# ads1299.net
KiCad netlist of a schematic drawn in Altium Designer
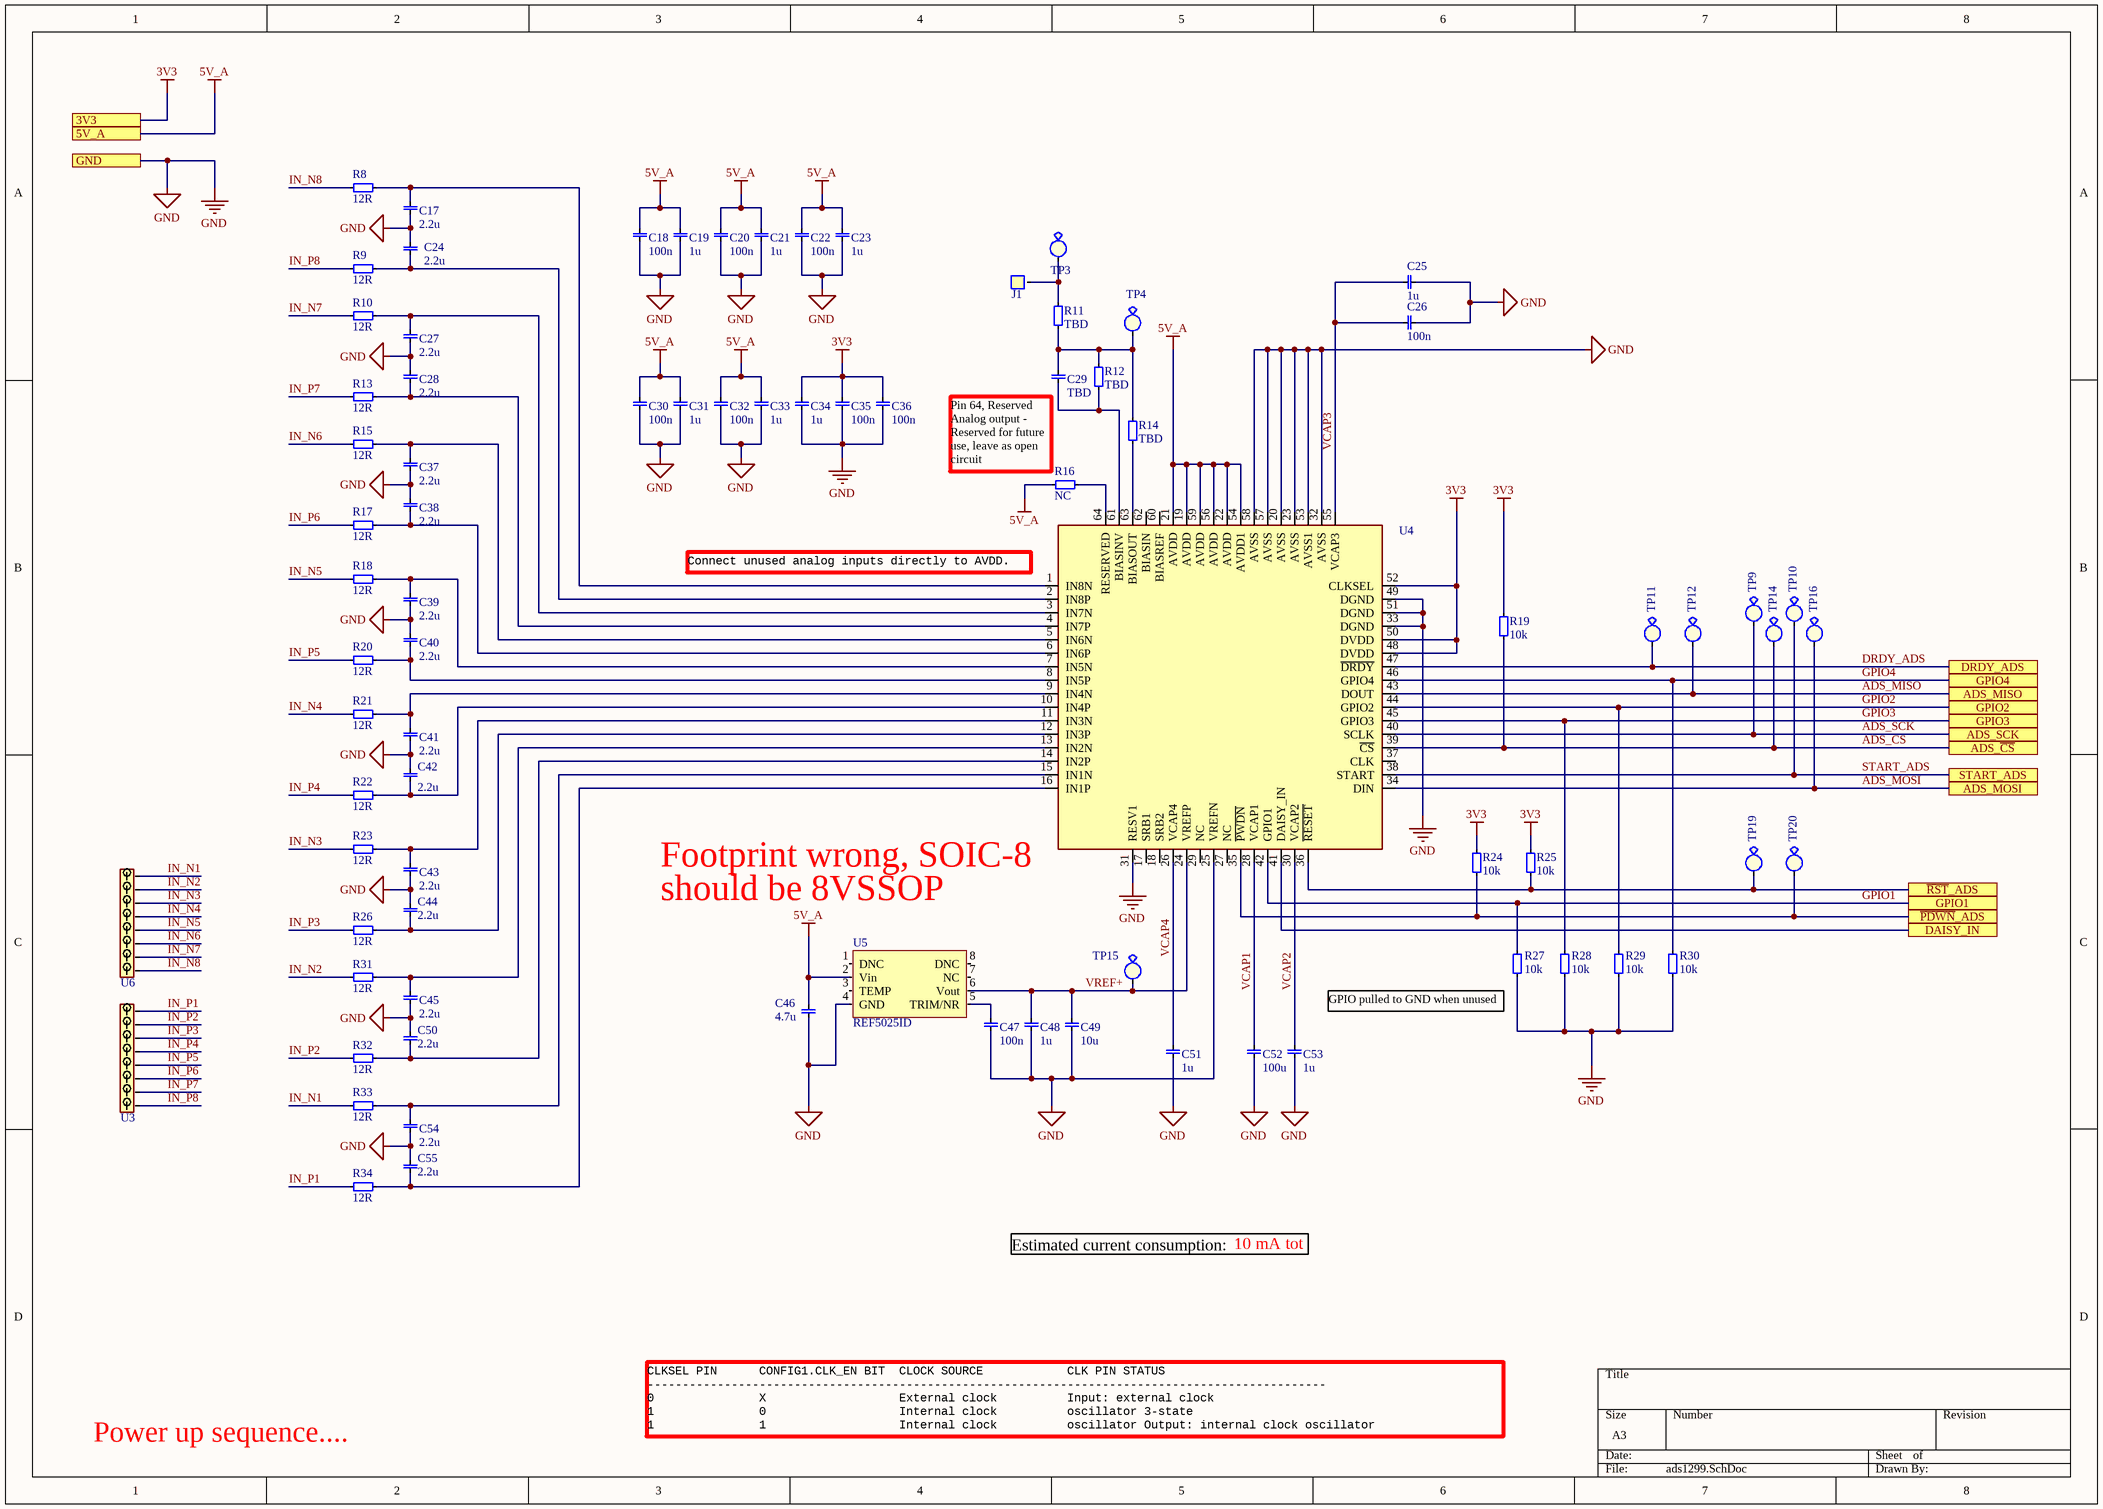
[diagram p0: ads1299.SchDoc]

(export (version "E")
  (design (tool "Eeschema 10.0.6"))
  (components
    (comp (ref "C17")
      (value "2.2u")
      (footprint "0402 CAP")
      (fields
        (field (name "MANUFACTURER PART NO") "GRM155D71A225ME15D")
        (field (name "Comment") "0603, capacitor")
      )
      (libsource (lib "jclib") (part "0603, capacitor"))
    )
    (comp (ref "C18")
      (value "100n")
      (footprint "0402 CAP")
      (fields
        (field (name "MANUFACTURER PART NO") "GRM155R62A104KE14D")
        (field (name "Comment") "0603, capacitor")
      )
      (libsource (lib "jclib") (part "0603, capacitor"))
    )
    (comp (ref "C19")
      (value "1u")
      (footprint "0402 CAP")
      (fields
        (field (name "MANUFACTURER PART NO") "CL05A105KO5NNNC")
        (field (name "Comment") "0603, capacitor")
      )
      (libsource (lib "jclib") (part "0603, capacitor"))
    )
    (comp (ref "C20")
      (value "100n")
      (footprint "0402 CAP")
      (fields
        (field (name "MANUFACTURER PART NO") "GRM155R62A104KE14D")
        (field (name "Comment") "0603, capacitor")
      )
      (libsource (lib "jclib") (part "0603, capacitor"))
    )
    (comp (ref "C21")
      (value "1u")
      (footprint "0402 CAP")
      (fields
        (field (name "MANUFACTURER PART NO") "CL05A105KO5NNNC")
        (field (name "Comment") "0603, capacitor")
      )
      (libsource (lib "jclib") (part "0603, capacitor"))
    )
    (comp (ref "C22")
      (value "100n")
      (footprint "0402 CAP")
      (fields
        (field (name "MANUFACTURER PART NO") "GRM155R62A104KE14D")
        (field (name "Comment") "0603, capacitor")
      )
      (libsource (lib "jclib") (part "0603, capacitor"))
    )
    (comp (ref "C23")
      (value "1u")
      (footprint "0402 CAP")
      (fields
        (field (name "MANUFACTURER PART NO") "CL05A105KO5NNNC")
        (field (name "Comment") "0603, capacitor")
      )
      (libsource (lib "jclib") (part "0603, capacitor"))
    )
    (comp (ref "C24")
      (value "2.2u")
      (footprint "0402 CAP")
      (fields
        (field (name "MANUFACTURER PART NO") "GRM155D71A225ME15D")
        (field (name "Comment") "0603, capacitor")
      )
      (libsource (lib "jclib") (part "0603, capacitor"))
    )
    (comp (ref "C25")
      (value "1u")
      (footprint "0402 CAP")
      (fields
        (field (name "MANUFACTURER PART NO") "CL05A105KO5NNNC")
        (field (name "Comment") "0603, capacitor")
      )
      (libsource (lib "jclib") (part "0603, capacitor"))
    )
    (comp (ref "C26")
      (value "100n")
      (footprint "0402 CAP")
      (fields
        (field (name "MANUFACTURER PART NO") "GRM155R62A104KE14D")
        (field (name "Comment") "0603, capacitor")
      )
      (libsource (lib "jclib") (part "0603, capacitor"))
    )
    (comp (ref "C27")
      (value "2.2u")
      (footprint "0402 CAP")
      (fields
        (field (name "MANUFACTURER PART NO") "GRM155D71A225ME15D")
        (field (name "Comment") "0603, capacitor")
      )
      (libsource (lib "jclib") (part "0603, capacitor"))
    )
    (comp (ref "C28")
      (value "2.2u")
      (footprint "0402 CAP")
      (fields
        (field (name "MANUFACTURER PART NO") "GRM155D71A225ME15D")
        (field (name "Comment") "0603, capacitor")
      )
      (libsource (lib "jclib") (part "0603, capacitor"))
    )
    (comp (ref "C29")
      (value "TBD")
      (footprint "0402 CAP")
      (fields (field (name "Comment") "0603, capacitor"))
      (libsource (lib "jclib") (part "0603, capacitor"))
    )
    (comp (ref "C30")
      (value "100n")
      (footprint "0402 CAP")
      (fields
        (field (name "MANUFACTURER PART NO") "GRM155R62A104KE14D")
        (field (name "Comment") "0603, capacitor")
      )
      (libsource (lib "jclib") (part "0603, capacitor"))
    )
    (comp (ref "C31")
      (value "1u")
      (footprint "0402 CAP")
      (fields
        (field (name "MANUFACTURER PART NO") "CL05A105KO5NNNC")
        (field (name "Comment") "0603, capacitor")
      )
      (libsource (lib "jclib") (part "0603, capacitor"))
    )
    (comp (ref "C32")
      (value "100n")
      (footprint "0402 CAP")
      (fields
        (field (name "MANUFACTURER PART NO") "GRM155R62A104KE14D")
        (field (name "Comment") "0603, capacitor")
      )
      (libsource (lib "jclib") (part "0603, capacitor"))
    )
    (comp (ref "C33")
      (value "1u")
      (footprint "0402 CAP")
      (fields
        (field (name "MANUFACTURER PART NO") "CL05A105KO5NNNC")
        (field (name "Comment") "0603, capacitor")
      )
      (libsource (lib "jclib") (part "0603, capacitor"))
    )
    (comp (ref "C34")
      (value "1u")
      (footprint "0402 CAP")
      (fields
        (field (name "MANUFACTURER PART NO") "CL05A105KO5NNNC")
        (field (name "Comment") "0603, capacitor")
      )
      (libsource (lib "jclib") (part "0603, capacitor"))
    )
    (comp (ref "C35")
      (value "100n")
      (footprint "0402 CAP")
      (fields
        (field (name "MANUFACTURER PART NO") "GRM155R62A104KE14D")
        (field (name "Comment") "0603, capacitor")
      )
      (libsource (lib "jclib") (part "0603, capacitor"))
    )
    (comp (ref "C36")
      (value "100n")
      (footprint "0402 CAP")
      (fields
        (field (name "MANUFACTURER PART NO") "GRM155R62A104KE14D")
        (field (name "Comment") "0603, capacitor")
      )
      (libsource (lib "jclib") (part "0603, capacitor"))
    )
    (comp (ref "C37")
      (value "2.2u")
      (footprint "0402 CAP")
      (fields
        (field (name "MANUFACTURER PART NO") "GRM155D71A225ME15D")
        (field (name "Comment") "0603, capacitor")
      )
      (libsource (lib "jclib") (part "0603, capacitor"))
    )
    (comp (ref "C38")
      (value "2.2u")
      (footprint "0402 CAP")
      (fields
        (field (name "MANUFACTURER PART NO") "GRM155D71A225ME15D")
        (field (name "Comment") "0603, capacitor")
      )
      (libsource (lib "jclib") (part "0603, capacitor"))
    )
    (comp (ref "C39")
      (value "2.2u")
      (footprint "0402 CAP")
      (fields
        (field (name "MANUFACTURER PART NO") "GRM155D71A225ME15D")
        (field (name "Comment") "0603, capacitor")
      )
      (libsource (lib "jclib") (part "0603, capacitor"))
    )
    (comp (ref "C40")
      (value "2.2u")
      (footprint "0402 CAP")
      (fields
        (field (name "MANUFACTURER PART NO") "GRM155D71A225ME15D")
        (field (name "Comment") "0603, capacitor")
      )
      (libsource (lib "jclib") (part "0603, capacitor"))
    )
    (comp (ref "C41")
      (value "2.2u")
      (footprint "0402 CAP")
      (fields
        (field (name "MANUFACTURER PART NO") "GRM155D71A225ME15D")
        (field (name "Comment") "0603, capacitor")
      )
      (libsource (lib "jclib") (part "0603, capacitor"))
    )
    (comp (ref "C42")
      (value "2.2u")
      (footprint "0402 CAP")
      (fields
        (field (name "MANUFACTURER PART NO") "GRM155D71A225ME15D")
        (field (name "Comment") "0603, capacitor")
      )
      (libsource (lib "jclib") (part "0603, capacitor"))
    )
    (comp (ref "C43")
      (value "2.2u")
      (footprint "0402 CAP")
      (fields
        (field (name "MANUFACTURER PART NO") "GRM155D71A225ME15D")
        (field (name "Comment") "0603, capacitor")
      )
      (libsource (lib "jclib") (part "0603, capacitor"))
    )
    (comp (ref "C44")
      (value "2.2u")
      (footprint "0402 CAP")
      (fields
        (field (name "MANUFACTURER PART NO") "GRM155D71A225ME15D")
        (field (name "Comment") "0603, capacitor")
      )
      (libsource (lib "jclib") (part "0603, capacitor"))
    )
    (comp (ref "C45")
      (value "2.2u")
      (footprint "0402 CAP")
      (fields
        (field (name "MANUFACTURER PART NO") "GRM155D71A225ME15D")
        (field (name "Comment") "0603, capacitor")
      )
      (libsource (lib "jclib") (part "0603, capacitor"))
    )
    (comp (ref "C46")
      (value "4.7u")
      (footprint "0402 CAP")
      (fields
        (field (name "MANUFACTURER PART NO") "04023U4R7CAT2A")
        (field (name "Comment") "0603, capacitor")
      )
      (libsource (lib "jclib") (part "0603, capacitor"))
    )
    (comp (ref "C47")
      (value "100n")
      (footprint "0402 CAP")
      (fields
        (field (name "MANUFACTURER PART NO") "GRM155R62A104KE14D")
        (field (name "Comment") "0603, capacitor")
      )
      (libsource (lib "jclib") (part "0603, capacitor"))
    )
    (comp (ref "C48")
      (value "1u")
      (footprint "0402 CAP")
      (fields
        (field (name "MANUFACTURER PART NO") "CL05A105KO5NNNC")
        (field (name "Comment") "0603, capacitor")
      )
      (libsource (lib "jclib") (part "0603, capacitor"))
    )
    (comp (ref "C49")
      (value "10u")
      (footprint "0402 CAP")
      (fields
        (field (name "MANUFACTURER PART NO") "GRM155R61A106ME11D")
        (field (name "Comment") "0603, capacitor")
      )
      (libsource (lib "jclib") (part "0603, capacitor"))
    )
    (comp (ref "C50")
      (value "2.2u")
      (footprint "0402 CAP")
      (fields
        (field (name "MANUFACTURER PART NO") "GRM155D71A225ME15D")
        (field (name "Comment") "0603, capacitor")
      )
      (libsource (lib "jclib") (part "0603, capacitor"))
    )
    (comp (ref "C51")
      (value "1u")
      (footprint "0402 CAP")
      (fields
        (field (name "MANUFACTURER PART NO") "CL05A105KO5NNNC")
        (field (name "Comment") "0603, capacitor")
      )
      (libsource (lib "jclib") (part "0603, capacitor"))
    )
    (comp (ref "C52")
      (value "100u")
      (footprint "1210, cap")
      (fields
        (field (name "MANUFACTURER PART NO") "EMK325ABJ107MM-T")
        (field (name "Comment") "1210, capacitor")
      )
      (libsource (lib "jclib") (part "1210, capacitor"))
    )
    (comp (ref "C53")
      (value "1u")
      (footprint "0402 CAP")
      (fields
        (field (name "MANUFACTURER PART NO") "CL05A105KO5NNNC")
        (field (name "Comment") "0603, capacitor")
      )
      (libsource (lib "jclib") (part "0603, capacitor"))
    )
    (comp (ref "C54")
      (value "2.2u")
      (footprint "0402 CAP")
      (fields
        (field (name "MANUFACTURER PART NO") "GRM155D71A225ME15D")
        (field (name "Comment") "0603, capacitor")
      )
      (libsource (lib "jclib") (part "0603, capacitor"))
    )
    (comp (ref "C55")
      (value "2.2u")
      (footprint "0402 CAP")
      (fields
        (field (name "MANUFACTURER PART NO") "GRM155D71A225ME15D")
        (field (name "Comment") "0603, capacitor")
      )
      (libsource (lib "jclib") (part "0603, capacitor"))
    )
    (comp (ref "J1")
      (value "1x1 Mini binding post")
      (footprint "1_pin_binding_post")
      (description "1 Pin Binding Post M2.5 Through Hole")
      (fields (field (name "MANUFACTURER PART NO") "8730"))
      (libsource (lib "jclib") (part "1x1 Mini binding post"))
    )
    (comp (ref "R8")
      (value "12R")
      (footprint "0402 res")
      (fields
        (field (name "MANUFACTURER PART NO") "RC0402FR-0712RL")
        (field (name "Comment") "0603, resistor")
      )
      (libsource (lib "jclib") (part "0603, resistor"))
    )
    (comp (ref "R9")
      (value "12R")
      (footprint "0402 res")
      (fields
        (field (name "MANUFACTURER PART NO") "RC0402FR-0712RL")
        (field (name "Comment") "0603, resistor")
      )
      (libsource (lib "jclib") (part "0603, resistor"))
    )
    (comp (ref "R10")
      (value "12R")
      (footprint "0402 res")
      (fields
        (field (name "MANUFACTURER PART NO") "RC0402FR-0712RL")
        (field (name "Comment") "0603, resistor")
      )
      (libsource (lib "jclib") (part "0603, resistor"))
    )
    (comp (ref "R11")
      (value "TBD")
      (footprint "0402 res")
      (fields (field (name "Comment") "0603, resistor"))
      (libsource (lib "jclib") (part "0603, resistor"))
    )
    (comp (ref "R12")
      (value "TBD")
      (footprint "0402 res")
      (fields (field (name "Comment") "0603, resistor"))
      (libsource (lib "jclib") (part "0603, resistor"))
    )
    (comp (ref "R13")
      (value "12R")
      (footprint "0402 res")
      (fields
        (field (name "MANUFACTURER PART NO") "RC0402FR-0712RL")
        (field (name "Comment") "0603, resistor")
      )
      (libsource (lib "jclib") (part "0603, resistor"))
    )
    (comp (ref "R14")
      (value "TBD")
      (footprint "0402 res")
      (fields (field (name "Comment") "0603, resistor"))
      (libsource (lib "jclib") (part "0603, resistor"))
    )
    (comp (ref "R15")
      (value "12R")
      (footprint "0402 res")
      (fields
        (field (name "MANUFACTURER PART NO") "RC0402FR-0712RL")
        (field (name "Comment") "0603, resistor")
      )
      (libsource (lib "jclib") (part "0603, resistor"))
    )
    (comp (ref "R16")
      (value "NC")
      (footprint "0402 res")
      (fields (field (name "Comment") "0603, resistor"))
      (libsource (lib "jclib") (part "0603, resistor"))
    )
    (comp (ref "R17")
      (value "12R")
      (footprint "0402 res")
      (fields
        (field (name "MANUFACTURER PART NO") "RC0402FR-0712RL")
        (field (name "Comment") "0603, resistor")
      )
      (libsource (lib "jclib") (part "0603, resistor"))
    )
    (comp (ref "R18")
      (value "12R")
      (footprint "0402 res")
      (fields
        (field (name "MANUFACTURER PART NO") "RC0402FR-0712RL")
        (field (name "Comment") "0603, resistor")
      )
      (libsource (lib "jclib") (part "0603, resistor"))
    )
    (comp (ref "R19")
      (value "10k")
      (footprint "0402 res")
      (fields
        (field (name "MANUFACTURER PART NO") "311-10.0KLRCT-ND")
        (field (name "Comment") "0603, resistor")
      )
      (libsource (lib "jclib") (part "0603, resistor"))
    )
    (comp (ref "R20")
      (value "12R")
      (footprint "0402 res")
      (fields
        (field (name "MANUFACTURER PART NO") "RC0402FR-0712RL")
        (field (name "Comment") "0603, resistor")
      )
      (libsource (lib "jclib") (part "0603, resistor"))
    )
    (comp (ref "R21")
      (value "12R")
      (footprint "0402 res")
      (fields
        (field (name "MANUFACTURER PART NO") "RC0402FR-0712RL")
        (field (name "Comment") "0603, resistor")
      )
      (libsource (lib "jclib") (part "0603, resistor"))
    )
    (comp (ref "R22")
      (value "12R")
      (footprint "0402 res")
      (fields
        (field (name "MANUFACTURER PART NO") "RC0402FR-0712RL")
        (field (name "Comment") "0603, resistor")
      )
      (libsource (lib "jclib") (part "0603, resistor"))
    )
    (comp (ref "R23")
      (value "12R")
      (footprint "0402 res")
      (fields
        (field (name "MANUFACTURER PART NO") "RC0402FR-0712RL")
        (field (name "Comment") "0603, resistor")
      )
      (libsource (lib "jclib") (part "0603, resistor"))
    )
    (comp (ref "R24")
      (value "10k")
      (footprint "0402 res")
      (fields
        (field (name "MANUFACTURER PART NO") "311-10.0KLRCT-ND")
        (field (name "Comment") "0603, resistor")
      )
      (libsource (lib "jclib") (part "0603, resistor"))
    )
    (comp (ref "R25")
      (value "10k")
      (footprint "0402 res")
      (fields
        (field (name "MANUFACTURER PART NO") "311-10.0KLRCT-ND")
        (field (name "Comment") "0603, resistor")
      )
      (libsource (lib "jclib") (part "0603, resistor"))
    )
    (comp (ref "R26")
      (value "12R")
      (footprint "0402 res")
      (fields
        (field (name "MANUFACTURER PART NO") "RC0402FR-0712RL")
        (field (name "Comment") "0603, resistor")
      )
      (libsource (lib "jclib") (part "0603, resistor"))
    )
    (comp (ref "R27")
      (value "10k")
      (footprint "0402 res")
      (fields
        (field (name "MANUFACTURER PART NO") "311-10.0KLRCT-ND")
        (field (name "Comment") "0603, resistor")
      )
      (libsource (lib "jclib") (part "0603, resistor"))
    )
    (comp (ref "R28")
      (value "10k")
      (footprint "0402 res")
      (fields
        (field (name "MANUFACTURER PART NO") "311-10.0KLRCT-ND")
        (field (name "Comment") "0603, resistor")
      )
      (libsource (lib "jclib") (part "0603, resistor"))
    )
    (comp (ref "R29")
      (value "10k")
      (footprint "0402 res")
      (fields
        (field (name "MANUFACTURER PART NO") "311-10.0KLRCT-ND")
        (field (name "Comment") "0603, resistor")
      )
      (libsource (lib "jclib") (part "0603, resistor"))
    )
    (comp (ref "R30")
      (value "10k")
      (footprint "0402 res")
      (fields
        (field (name "MANUFACTURER PART NO") "311-10.0KLRCT-ND")
        (field (name "Comment") "0603, resistor")
      )
      (libsource (lib "jclib") (part "0603, resistor"))
    )
    (comp (ref "R31")
      (value "12R")
      (footprint "0402 res")
      (fields
        (field (name "MANUFACTURER PART NO") "RC0402FR-0712RL")
        (field (name "Comment") "0603, resistor")
      )
      (libsource (lib "jclib") (part "0603, resistor"))
    )
    (comp (ref "R32")
      (value "12R")
      (footprint "0402 res")
      (fields
        (field (name "MANUFACTURER PART NO") "RC0402FR-0712RL")
        (field (name "Comment") "0603, resistor")
      )
      (libsource (lib "jclib") (part "0603, resistor"))
    )
    (comp (ref "R33")
      (value "12R")
      (footprint "0402 res")
      (fields
        (field (name "MANUFACTURER PART NO") "RC0402FR-0712RL")
        (field (name "Comment") "0603, resistor")
      )
      (libsource (lib "jclib") (part "0603, resistor"))
    )
    (comp (ref "R34")
      (value "12R")
      (footprint "0402 res")
      (fields
        (field (name "MANUFACTURER PART NO") "RC0402FR-0712RL")
        (field (name "Comment") "0603, resistor")
      )
      (libsource (lib "jclib") (part "0603, resistor"))
    )
    (comp (ref "TP3")
      (value "Test Point")
      (footprint "TESTPOINT_SMD")
      (libsource (lib "jclib") (part "Test Point"))
    )
    (comp (ref "TP4")
      (value "Test Point")
      (footprint "TESTPOINT_SMD")
      (libsource (lib "jclib") (part "Test Point"))
    )
    (comp (ref "TP9")
      (value "Test Point")
      (footprint "TESTPOINT_SMD")
      (libsource (lib "jclib") (part "Test Point"))
    )
    (comp (ref "TP10")
      (value "Test Point")
      (footprint "TESTPOINT_SMD")
      (libsource (lib "jclib") (part "Test Point"))
    )
    (comp (ref "TP11")
      (value "Test Point")
      (footprint "TESTPOINT_SMD")
      (libsource (lib "jclib") (part "Test Point"))
    )
    (comp (ref "TP12")
      (value "Test Point")
      (footprint "TESTPOINT_SMD")
      (libsource (lib "jclib") (part "Test Point"))
    )
    (comp (ref "TP14")
      (value "Test Point")
      (footprint "TESTPOINT_SMD")
      (libsource (lib "jclib") (part "Test Point"))
    )
    (comp (ref "TP15")
      (value "Test Point")
      (footprint "TESTPOINT_SMD")
      (libsource (lib "jclib") (part "Test Point"))
    )
    (comp (ref "TP16")
      (value "Test Point")
      (footprint "TESTPOINT_SMD")
      (libsource (lib "jclib") (part "Test Point"))
    )
    (comp (ref "TP19")
      (value "Test Point")
      (footprint "TESTPOINT_SMD")
      (libsource (lib "jclib") (part "Test Point"))
    )
    (comp (ref "TP20")
      (value "Test Point")
      (footprint "TESTPOINT_SMD")
      (libsource (lib "jclib") (part "Test Point"))
    )
    (comp (ref "U3")
      (value "1x8 Screw terminal")
      (footprint "screw_term_8_pos")
      (fields (field (name "MANUFACTURER PART NO") "OSTVN08A150"))
      (libsource (lib "") (part "1x8 Screw terminal_1"))
    )
    (comp (ref "U4")
      (value "ADS1299")
      (footprint "TQFP64_05MM_P")
      (description "24-Bit, Analog-to-Digital Converter for EEG and\r\nBiopotential Measurements")
      (fields (field (name "MANUFACTURER PART NO") "ADS1299IPAG"))
      (libsource (lib "jclib") (part "ADS1299"))
    )
    (comp (ref "U5")
      (value "REF5025ID")
      (footprint "SOP65P490X110-8N")
      (libsource (lib "jclib") (part "REF5025ID"))
    )
    (comp (ref "U6")
      (value "1x8 Screw terminal")
      (footprint "screw_term_8_pos")
      (fields (field (name "MANUFACTURER PART NO") "OSTVN08A150"))
      (libsource (lib "jclib") (part "1x8 Screw terminal"))
    )
  )
  (nets
    (net (code "1") (name "/ADS_MISO") (class "Default")
      (node (ref "TP12") (pin "0") (pinfunction "0_0") (pintype "passive"))
      (node (ref "U4") (pin "43") (pinfunction "DOUT_43") (pintype "passive"))
    )
    (net (code "2") (name "/ADS_MOSI") (class "Default")
      (node (ref "TP16") (pin "0") (pinfunction "0_0") (pintype "passive"))
      (node (ref "U4") (pin "34") (pinfunction "DIN_34") (pintype "passive"))
    )
    (net (code "3") (name "/ADS_SCK") (class "Default")
      (node (ref "TP9") (pin "0") (pinfunction "0_0") (pintype "passive"))
      (node (ref "U4") (pin "40") (pinfunction "SCLK_40") (pintype "passive"))
    )
    (net (code "4") (name "/ADS_~{CS}") (class "Default")
      (node (ref "R19") (pin "1") (pinfunction "1_1") (pintype "passive"))
      (node (ref "TP14") (pin "0") (pinfunction "0_0") (pintype "passive"))
      (node (ref "U4") (pin "39") (pinfunction "~{CS}_39") (pintype "passive"))
    )
    (net (code "5") (name "/DAISY_IN") (class "Default")
      (node (ref "U4") (pin "41") (pinfunction "DAISY_IN_41") (pintype "passive"))
    )
    (net (code "6") (name "/DRDY_ADS") (class "Default")
      (node (ref "TP11") (pin "0") (pinfunction "0_0") (pintype "passive"))
      (node (ref "U4") (pin "47") (pinfunction "~{DRDY}_47") (pintype "passive"))
    )
    (net (code "7") (name "/GPIO1") (class "Default")
      (node (ref "R27") (pin "0") (pinfunction "0_0") (pintype "passive"))
      (node (ref "U4") (pin "42") (pinfunction "GPIO1_42") (pintype "passive"))
    )
    (net (code "8") (name "/GPIO2") (class "Default")
      (node (ref "R29") (pin "0") (pinfunction "0_0") (pintype "passive"))
      (node (ref "U4") (pin "44") (pinfunction "GPIO2_44") (pintype "passive"))
    )
    (net (code "9") (name "/GPIO3") (class "Default")
      (node (ref "R28") (pin "0") (pinfunction "0_0") (pintype "passive"))
      (node (ref "U4") (pin "45") (pinfunction "GPIO3_45") (pintype "passive"))
    )
    (net (code "10") (name "/GPIO4") (class "Default")
      (node (ref "R30") (pin "0") (pinfunction "0_0") (pintype "passive"))
      (node (ref "U4") (pin "46") (pinfunction "GPIO4_46") (pintype "passive"))
    )
    (net (code "11") (name "/IN_N1") (class "Default")
      (node (ref "R33") (pin "1") (pinfunction "1_1") (pintype "passive"))
      (node (ref "U6") (pin "1") (pinfunction "1_1") (pintype "passive"))
    )
    (net (code "12") (name "/IN_N2") (class "Default")
      (node (ref "R31") (pin "1") (pinfunction "1_1") (pintype "passive"))
      (node (ref "U6") (pin "2") (pinfunction "2_2") (pintype "passive"))
    )
    (net (code "13") (name "/IN_N3") (class "Default")
      (node (ref "R23") (pin "1") (pinfunction "1_1") (pintype "passive"))
      (node (ref "U6") (pin "3") (pinfunction "3_3") (pintype "passive"))
    )
    (net (code "14") (name "/IN_N4") (class "Default")
      (node (ref "R21") (pin "1") (pinfunction "1_1") (pintype "passive"))
      (node (ref "U6") (pin "4") (pinfunction "4_4") (pintype "passive"))
    )
    (net (code "15") (name "/IN_N5") (class "Default")
      (node (ref "R18") (pin "1") (pinfunction "1_1") (pintype "passive"))
      (node (ref "U6") (pin "5") (pinfunction "5_5") (pintype "passive"))
    )
    (net (code "16") (name "/IN_N6") (class "Default")
      (node (ref "R15") (pin "1") (pinfunction "1_1") (pintype "passive"))
      (node (ref "U6") (pin "6") (pinfunction "6_6") (pintype "passive"))
    )
    (net (code "17") (name "/IN_N7") (class "Default")
      (node (ref "R10") (pin "1") (pinfunction "1_1") (pintype "passive"))
      (node (ref "U6") (pin "7") (pinfunction "7_7") (pintype "passive"))
    )
    (net (code "18") (name "/IN_N8") (class "Default")
      (node (ref "R8") (pin "1") (pinfunction "1_1") (pintype "passive"))
      (node (ref "U6") (pin "8") (pinfunction "8_8") (pintype "passive"))
    )
    (net (code "19") (name "/IN_P1") (class "Default")
      (node (ref "R34") (pin "1") (pinfunction "1_1") (pintype "passive"))
      (node (ref "U3") (pin "8") (pinfunction "8_8") (pintype "passive"))
    )
    (net (code "20") (name "/IN_P2") (class "Default")
      (node (ref "R32") (pin "1") (pinfunction "1_1") (pintype "passive"))
      (node (ref "U3") (pin "7") (pinfunction "7_7") (pintype "passive"))
    )
    (net (code "21") (name "/IN_P3") (class "Default")
      (node (ref "R26") (pin "1") (pinfunction "1_1") (pintype "passive"))
      (node (ref "U3") (pin "6") (pinfunction "6_6") (pintype "passive"))
    )
    (net (code "22") (name "/IN_P4") (class "Default")
      (node (ref "R22") (pin "1") (pinfunction "1_1") (pintype "passive"))
      (node (ref "U3") (pin "5") (pinfunction "5_5") (pintype "passive"))
    )
    (net (code "23") (name "/IN_P5") (class "Default")
      (node (ref "R20") (pin "1") (pinfunction "1_1") (pintype "passive"))
      (node (ref "U3") (pin "4") (pinfunction "4_4") (pintype "passive"))
    )
    (net (code "24") (name "/IN_P6") (class "Default")
      (node (ref "R17") (pin "1") (pinfunction "1_1") (pintype "passive"))
      (node (ref "U3") (pin "3") (pinfunction "3_3") (pintype "passive"))
    )
    (net (code "25") (name "/IN_P7") (class "Default")
      (node (ref "R13") (pin "1") (pinfunction "1_1") (pintype "passive"))
      (node (ref "U3") (pin "2") (pinfunction "2_2") (pintype "passive"))
    )
    (net (code "26") (name "/IN_P8") (class "Default")
      (node (ref "R9") (pin "1") (pinfunction "1_1") (pintype "passive"))
      (node (ref "U3") (pin "1") (pinfunction "1_1") (pintype "passive"))
    )
    (net (code "27") (name "/START_ADS") (class "Default")
      (node (ref "TP10") (pin "0") (pinfunction "0_0") (pintype "passive"))
      (node (ref "U4") (pin "38") (pinfunction "START_38") (pintype "passive"))
    )
    (net (code "28") (name "/VCAP1") (class "Default")
      (node (ref "C52") (pin "1") (pinfunction "1_1") (pintype "passive"))
      (node (ref "U4") (pin "28") (pinfunction "VCAP1_28") (pintype "passive"))
    )
    (net (code "29") (name "/VCAP2") (class "Default")
      (node (ref "C53") (pin "1") (pinfunction "1_1") (pintype "passive"))
      (node (ref "U4") (pin "30") (pinfunction "VCAP2_30") (pintype "passive"))
    )
    (net (code "30") (name "/VCAP3") (class "Default")
      (node (ref "C25") (pin "1") (pinfunction "1_1") (pintype "passive"))
      (node (ref "C26") (pin "1") (pinfunction "1_1") (pintype "passive"))
      (node (ref "U4") (pin "55") (pinfunction "VCAP3_55") (pintype "passive"))
    )
    (net (code "31") (name "/VCAP4") (class "Default")
      (node (ref "C51") (pin "1") (pinfunction "1_1") (pintype "passive"))
      (node (ref "U4") (pin "26") (pinfunction "VCAP4_26") (pintype "passive"))
    )
    (net (code "32") (name "/VREF+") (class "Default")
      (node (ref "C48") (pin "1") (pinfunction "1_1") (pintype "passive"))
      (node (ref "C49") (pin "1") (pinfunction "1_1") (pintype "passive"))
      (node (ref "TP15") (pin "0") (pinfunction "0_0") (pintype "passive"))
      (node (ref "U4") (pin "24") (pinfunction "VREFP_24") (pintype "passive"))
      (node (ref "U5") (pin "6") (pinfunction "Vout_6") (pintype "passive"))
    )
    (net (code "33") (name "/~{PDWN}_ADS") (class "Default")
      (node (ref "R24") (pin "1") (pinfunction "1_1") (pintype "passive"))
      (node (ref "TP20") (pin "0") (pinfunction "0_0") (pintype "passive"))
      (node (ref "U4") (pin "35") (pinfunction "~{PWDN}_35") (pintype "passive"))
    )
    (net (code "34") (name "/~{RST}_ADS") (class "Default")
      (node (ref "R25") (pin "1") (pinfunction "1_1") (pintype "passive"))
      (node (ref "TP19") (pin "0") (pinfunction "0_0") (pintype "passive"))
      (node (ref "U4") (pin "36") (pinfunction "~{RESET}_36") (pintype "passive"))
    )
    (net (code "35") (name "3V3") (class "Default")
      (node (ref "C34") (pin "1") (pinfunction "1_1") (pintype "passive"))
      (node (ref "C35") (pin "1") (pinfunction "1_1") (pintype "passive"))
      (node (ref "C36") (pin "1") (pinfunction "1_1") (pintype "passive"))
      (node (ref "R19") (pin "0") (pinfunction "0_0") (pintype "passive"))
      (node (ref "R24") (pin "0") (pinfunction "0_0") (pintype "passive"))
      (node (ref "R25") (pin "0") (pinfunction "0_0") (pintype "passive"))
      (node (ref "U4") (pin "48") (pinfunction "DVDD_48") (pintype "passive"))
      (node (ref "U4") (pin "50") (pinfunction "DVDD_50") (pintype "passive"))
      (node (ref "U4") (pin "52") (pinfunction "CLKSEL_52") (pintype "passive"))
    )
    (net (code "36") (name "5V_A") (class "Default")
      (node (ref "C18") (pin "1") (pinfunction "1_1") (pintype "passive"))
      (node (ref "C19") (pin "1") (pinfunction "1_1") (pintype "passive"))
      (node (ref "C20") (pin "1") (pinfunction "1_1") (pintype "passive"))
      (node (ref "C21") (pin "1") (pinfunction "1_1") (pintype "passive"))
      (node (ref "C22") (pin "1") (pinfunction "1_1") (pintype "passive"))
      (node (ref "C23") (pin "1") (pinfunction "1_1") (pintype "passive"))
      (node (ref "C30") (pin "1") (pinfunction "1_1") (pintype "passive"))
      (node (ref "C31") (pin "1") (pinfunction "1_1") (pintype "passive"))
      (node (ref "C32") (pin "1") (pinfunction "1_1") (pintype "passive"))
      (node (ref "C33") (pin "1") (pinfunction "1_1") (pintype "passive"))
      (node (ref "C46") (pin "1") (pinfunction "1_1") (pintype "passive"))
      (node (ref "R16") (pin "0") (pinfunction "0_0") (pintype "passive"))
      (node (ref "U4") (pin "19") (pinfunction "AVDD_19") (pintype "passive"))
      (node (ref "U4") (pin "21") (pinfunction "AVDD_21") (pintype "passive"))
      (node (ref "U4") (pin "22") (pinfunction "AVDD_22") (pintype "passive"))
      (node (ref "U4") (pin "54") (pinfunction "AVDD1_54") (pintype "passive"))
      (node (ref "U4") (pin "56") (pinfunction "AVDD_56") (pintype "passive"))
      (node (ref "U4") (pin "59") (pinfunction "AVDD_59") (pintype "passive"))
      (node (ref "U5") (pin "2") (pinfunction "Vin_2") (pintype "passive"))
    )
    (net (code "37") (name "GND") (class "Default")
      (node (ref "C17") (pin "0") (pinfunction "0_0") (pintype "passive"))
      (node (ref "C18") (pin "0") (pinfunction "0_0") (pintype "passive"))
      (node (ref "C19") (pin "0") (pinfunction "0_0") (pintype "passive"))
      (node (ref "C20") (pin "0") (pinfunction "0_0") (pintype "passive"))
      (node (ref "C21") (pin "0") (pinfunction "0_0") (pintype "passive"))
      (node (ref "C22") (pin "0") (pinfunction "0_0") (pintype "passive"))
      (node (ref "C23") (pin "0") (pinfunction "0_0") (pintype "passive"))
      (node (ref "C24") (pin "0") (pinfunction "0_0") (pintype "passive"))
      (node (ref "C25") (pin "0") (pinfunction "0_0") (pintype "passive"))
      (node (ref "C26") (pin "0") (pinfunction "0_0") (pintype "passive"))
      (node (ref "C27") (pin "0") (pinfunction "0_0") (pintype "passive"))
      (node (ref "C28") (pin "0") (pinfunction "0_0") (pintype "passive"))
      (node (ref "C30") (pin "0") (pinfunction "0_0") (pintype "passive"))
      (node (ref "C31") (pin "0") (pinfunction "0_0") (pintype "passive"))
      (node (ref "C32") (pin "0") (pinfunction "0_0") (pintype "passive"))
      (node (ref "C33") (pin "0") (pinfunction "0_0") (pintype "passive"))
      (node (ref "C34") (pin "0") (pinfunction "0_0") (pintype "passive"))
      (node (ref "C35") (pin "0") (pinfunction "0_0") (pintype "passive"))
      (node (ref "C36") (pin "0") (pinfunction "0_0") (pintype "passive"))
      (node (ref "C37") (pin "0") (pinfunction "0_0") (pintype "passive"))
      (node (ref "C38") (pin "0") (pinfunction "0_0") (pintype "passive"))
      (node (ref "C39") (pin "0") (pinfunction "0_0") (pintype "passive"))
      (node (ref "C40") (pin "0") (pinfunction "0_0") (pintype "passive"))
      (node (ref "C41") (pin "0") (pinfunction "0_0") (pintype "passive"))
      (node (ref "C42") (pin "0") (pinfunction "0_0") (pintype "passive"))
      (node (ref "C43") (pin "0") (pinfunction "0_0") (pintype "passive"))
      (node (ref "C44") (pin "0") (pinfunction "0_0") (pintype "passive"))
      (node (ref "C45") (pin "0") (pinfunction "0_0") (pintype "passive"))
      (node (ref "C46") (pin "0") (pinfunction "0_0") (pintype "passive"))
      (node (ref "C47") (pin "0") (pinfunction "0_0") (pintype "passive"))
      (node (ref "C48") (pin "0") (pinfunction "0_0") (pintype "passive"))
      (node (ref "C49") (pin "0") (pinfunction "0_0") (pintype "passive"))
      (node (ref "C50") (pin "0") (pinfunction "0_0") (pintype "passive"))
      (node (ref "C51") (pin "0") (pinfunction "0_0") (pintype "passive"))
      (node (ref "C52") (pin "0") (pinfunction "0_0") (pintype "passive"))
      (node (ref "C53") (pin "0") (pinfunction "0_0") (pintype "passive"))
      (node (ref "C54") (pin "0") (pinfunction "0_0") (pintype "passive"))
      (node (ref "C55") (pin "0") (pinfunction "0_0") (pintype "passive"))
      (node (ref "R27") (pin "1") (pinfunction "1_1") (pintype "passive"))
      (node (ref "R28") (pin "1") (pinfunction "1_1") (pintype "passive"))
      (node (ref "R29") (pin "1") (pinfunction "1_1") (pintype "passive"))
      (node (ref "R30") (pin "1") (pinfunction "1_1") (pintype "passive"))
      (node (ref "U4") (pin "20") (pinfunction "AVSS_20") (pintype "passive"))
      (node (ref "U4") (pin "23") (pinfunction "AVSS_23") (pintype "passive"))
      (node (ref "U4") (pin "25") (pinfunction "VREFN_25") (pintype "passive"))
      (node (ref "U4") (pin "31") (pinfunction "RESV1_31") (pintype "passive"))
      (node (ref "U4") (pin "32") (pinfunction "AVSS_32") (pintype "passive"))
      (node (ref "U4") (pin "33") (pinfunction "DGND_33") (pintype "passive"))
      (node (ref "U4") (pin "49") (pinfunction "DGND_49") (pintype "passive"))
      (node (ref "U4") (pin "51") (pinfunction "DGND_51") (pintype "passive"))
      (node (ref "U4") (pin "53") (pinfunction "AVSS1_53") (pintype "passive"))
      (node (ref "U4") (pin "57") (pinfunction "AVSS_57") (pintype "passive"))
      (node (ref "U4") (pin "58") (pinfunction "AVSS_58") (pintype "passive"))
      (node (ref "U5") (pin "4") (pinfunction "GND_4") (pintype "passive"))
    )
    (net (code "38") (name "Net-(C29-Pad1)") (class "Default")
      (node (ref "C29") (pin "1") (pinfunction "1_1") (pintype "passive"))
      (node (ref "R11") (pin "1") (pinfunction "1_1") (pintype "passive"))
      (node (ref "R12") (pin "0") (pinfunction "0_0") (pintype "passive"))
      (node (ref "R14") (pin "0") (pinfunction "0_0") (pintype "passive"))
      (node (ref "TP4") (pin "0") (pinfunction "0_0") (pintype "passive"))
    )
    (net (code "39") (name "Net-(J1-Pad1)") (class "Default")
      (node (ref "J1") (pin "1") (pinfunction "1_1") (pintype "passive"))
      (node (ref "R11") (pin "0") (pinfunction "0_0") (pintype "passive"))
      (node (ref "TP3") (pin "0") (pinfunction "0_0") (pintype "passive"))
    )
    (net (code "40") (name "Net-(U4-BIASINV)") (class "Default")
      (node (ref "C29") (pin "0") (pinfunction "0_0") (pintype "passive"))
      (node (ref "R12") (pin "1") (pinfunction "1_1") (pintype "passive"))
      (node (ref "U4") (pin "61") (pinfunction "BIASINV_61") (pintype "passive"))
    )
    (net (code "41") (name "Net-(U4-BIASOUT)") (class "Default")
      (node (ref "R14") (pin "1") (pinfunction "1_1") (pintype "passive"))
      (node (ref "U4") (pin "63") (pinfunction "BIASOUT_63") (pintype "passive"))
    )
    (net (code "42") (name "Net-(U4-IN1N)") (class "Default")
      (node (ref "C54") (pin "1") (pinfunction "1_1") (pintype "passive"))
      (node (ref "R33") (pin "0") (pinfunction "0_0") (pintype "passive"))
      (node (ref "U4") (pin "15") (pinfunction "IN1N_15") (pintype "passive"))
    )
    (net (code "43") (name "Net-(U4-IN1P)") (class "Default")
      (node (ref "C55") (pin "1") (pinfunction "1_1") (pintype "passive"))
      (node (ref "R34") (pin "0") (pinfunction "0_0") (pintype "passive"))
      (node (ref "U4") (pin "16") (pinfunction "IN1P_16") (pintype "passive"))
    )
    (net (code "44") (name "Net-(U4-IN2N)") (class "Default")
      (node (ref "C45") (pin "1") (pinfunction "1_1") (pintype "passive"))
      (node (ref "R31") (pin "0") (pinfunction "0_0") (pintype "passive"))
      (node (ref "U4") (pin "13") (pinfunction "IN2N_13") (pintype "passive"))
    )
    (net (code "45") (name "Net-(U4-IN2P)") (class "Default")
      (node (ref "C50") (pin "1") (pinfunction "1_1") (pintype "passive"))
      (node (ref "R32") (pin "0") (pinfunction "0_0") (pintype "passive"))
      (node (ref "U4") (pin "14") (pinfunction "IN2P_14") (pintype "passive"))
    )
    (net (code "46") (name "Net-(U4-IN3N)") (class "Default")
      (node (ref "C43") (pin "1") (pinfunction "1_1") (pintype "passive"))
      (node (ref "R23") (pin "0") (pinfunction "0_0") (pintype "passive"))
      (node (ref "U4") (pin "11") (pinfunction "IN3N_11") (pintype "passive"))
    )
    (net (code "47") (name "Net-(U4-IN3P)") (class "Default")
      (node (ref "C44") (pin "1") (pinfunction "1_1") (pintype "passive"))
      (node (ref "R26") (pin "0") (pinfunction "0_0") (pintype "passive"))
      (node (ref "U4") (pin "12") (pinfunction "IN3P_12") (pintype "passive"))
    )
    (net (code "48") (name "Net-(U4-IN4N)") (class "Default")
      (node (ref "C41") (pin "1") (pinfunction "1_1") (pintype "passive"))
      (node (ref "R21") (pin "0") (pinfunction "0_0") (pintype "passive"))
      (node (ref "U4") (pin "9") (pinfunction "IN4N_9") (pintype "passive"))
    )
    (net (code "49") (name "Net-(U4-IN4P)") (class "Default")
      (node (ref "C42") (pin "1") (pinfunction "1_1") (pintype "passive"))
      (node (ref "R22") (pin "0") (pinfunction "0_0") (pintype "passive"))
      (node (ref "U4") (pin "10") (pinfunction "IN4P_10") (pintype "passive"))
    )
    (net (code "50") (name "Net-(U4-IN5N)") (class "Default")
      (node (ref "C39") (pin "1") (pinfunction "1_1") (pintype "passive"))
      (node (ref "R18") (pin "0") (pinfunction "0_0") (pintype "passive"))
      (node (ref "U4") (pin "7") (pinfunction "IN5N_7") (pintype "passive"))
    )
    (net (code "51") (name "Net-(U4-IN5P)") (class "Default")
      (node (ref "C40") (pin "1") (pinfunction "1_1") (pintype "passive"))
      (node (ref "R20") (pin "0") (pinfunction "0_0") (pintype "passive"))
      (node (ref "U4") (pin "8") (pinfunction "IN5P_8") (pintype "passive"))
    )
    (net (code "52") (name "Net-(U4-IN6N)") (class "Default")
      (node (ref "C37") (pin "1") (pinfunction "1_1") (pintype "passive"))
      (node (ref "R15") (pin "0") (pinfunction "0_0") (pintype "passive"))
      (node (ref "U4") (pin "5") (pinfunction "IN6N_5") (pintype "passive"))
    )
    (net (code "53") (name "Net-(U4-IN6P)") (class "Default")
      (node (ref "C38") (pin "1") (pinfunction "1_1") (pintype "passive"))
      (node (ref "R17") (pin "0") (pinfunction "0_0") (pintype "passive"))
      (node (ref "U4") (pin "6") (pinfunction "IN6P_6") (pintype "passive"))
    )
    (net (code "54") (name "Net-(U4-IN7N)") (class "Default")
      (node (ref "C27") (pin "1") (pinfunction "1_1") (pintype "passive"))
      (node (ref "R10") (pin "0") (pinfunction "0_0") (pintype "passive"))
      (node (ref "U4") (pin "3") (pinfunction "IN7N_3") (pintype "passive"))
    )
    (net (code "55") (name "Net-(U4-IN7P)") (class "Default")
      (node (ref "C28") (pin "1") (pinfunction "1_1") (pintype "passive"))
      (node (ref "R13") (pin "0") (pinfunction "0_0") (pintype "passive"))
      (node (ref "U4") (pin "4") (pinfunction "IN7P_4") (pintype "passive"))
    )
    (net (code "56") (name "Net-(U4-IN8N)") (class "Default")
      (node (ref "C17") (pin "1") (pinfunction "1_1") (pintype "passive"))
      (node (ref "R8") (pin "0") (pinfunction "0_0") (pintype "passive"))
      (node (ref "U4") (pin "1") (pinfunction "IN8N_1") (pintype "passive"))
    )
    (net (code "57") (name "Net-(U4-IN8P)") (class "Default")
      (node (ref "C24") (pin "1") (pinfunction "1_1") (pintype "passive"))
      (node (ref "R9") (pin "0") (pinfunction "0_0") (pintype "passive"))
      (node (ref "U4") (pin "2") (pinfunction "IN8P_2") (pintype "passive"))
    )
    (net (code "58") (name "Net-(U4-RESERVED)") (class "Default")
      (node (ref "R16") (pin "1") (pinfunction "1_1") (pintype "passive"))
      (node (ref "U4") (pin "64") (pinfunction "RESERVED_64") (pintype "passive"))
    )
    (net (code "59") (name "Net-(U5-TRIM{slash}NR)") (class "Default")
      (node (ref "C47") (pin "1") (pinfunction "1_1") (pintype "passive"))
      (node (ref "U5") (pin "5") (pinfunction "TRIM/NR_5") (pintype "passive"))
    )
    (net (code "60") (name "unconnected-(U4-BIASIN-Pad62)") (class "Default")
      (node (ref "U4") (pin "62") (pinfunction "BIASIN_62") (pintype "passive"))
    )
    (net (code "61") (name "unconnected-(U4-BIASREF-Pad60)") (class "Default")
      (node (ref "U4") (pin "60") (pinfunction "BIASREF_60") (pintype "passive"))
    )
    (net (code "62") (name "unconnected-(U4-CLK-Pad37)") (class "Default")
      (node (ref "U4") (pin "37") (pinfunction "CLK_37") (pintype "passive"))
    )
    (net (code "63") (name "unconnected-(U4-NC-Pad27)") (class "Default")
      (node (ref "U4") (pin "27") (pinfunction "NC_27") (pintype "passive"))
    )
    (net (code "64") (name "unconnected-(U4-NC-Pad29)") (class "Default")
      (node (ref "U4") (pin "29") (pinfunction "NC_29") (pintype "passive"))
    )
    (net (code "65") (name "unconnected-(U4-SRB1-Pad17)") (class "Default")
      (node (ref "U4") (pin "17") (pinfunction "SRB1_17") (pintype "passive"))
    )
    (net (code "66") (name "unconnected-(U4-SRB2-Pad18)") (class "Default")
      (node (ref "U4") (pin "18") (pinfunction "SRB2_18") (pintype "passive"))
    )
    (net (code "67") (name "unconnected-(U5-DNC-Pad1)") (class "Default")
      (node (ref "U5") (pin "1") (pinfunction "DNC_1") (pintype "passive"))
    )
    (net (code "68") (name "unconnected-(U5-DNC-Pad8)") (class "Default")
      (node (ref "U5") (pin "8") (pinfunction "DNC_8") (pintype "passive"))
    )
    (net (code "69") (name "unconnected-(U5-NC-Pad7)") (class "Default")
      (node (ref "U5") (pin "7") (pinfunction "NC_7") (pintype "passive"))
    )
    (net (code "70") (name "unconnected-(U5-TEMP-Pad3)") (class "Default")
      (node (ref "U5") (pin "3") (pinfunction "TEMP_3") (pintype "passive"))
    )
  )
)
